# Sensor_Board.net
KiCad netlist of a schematic drawn in Altium Designer
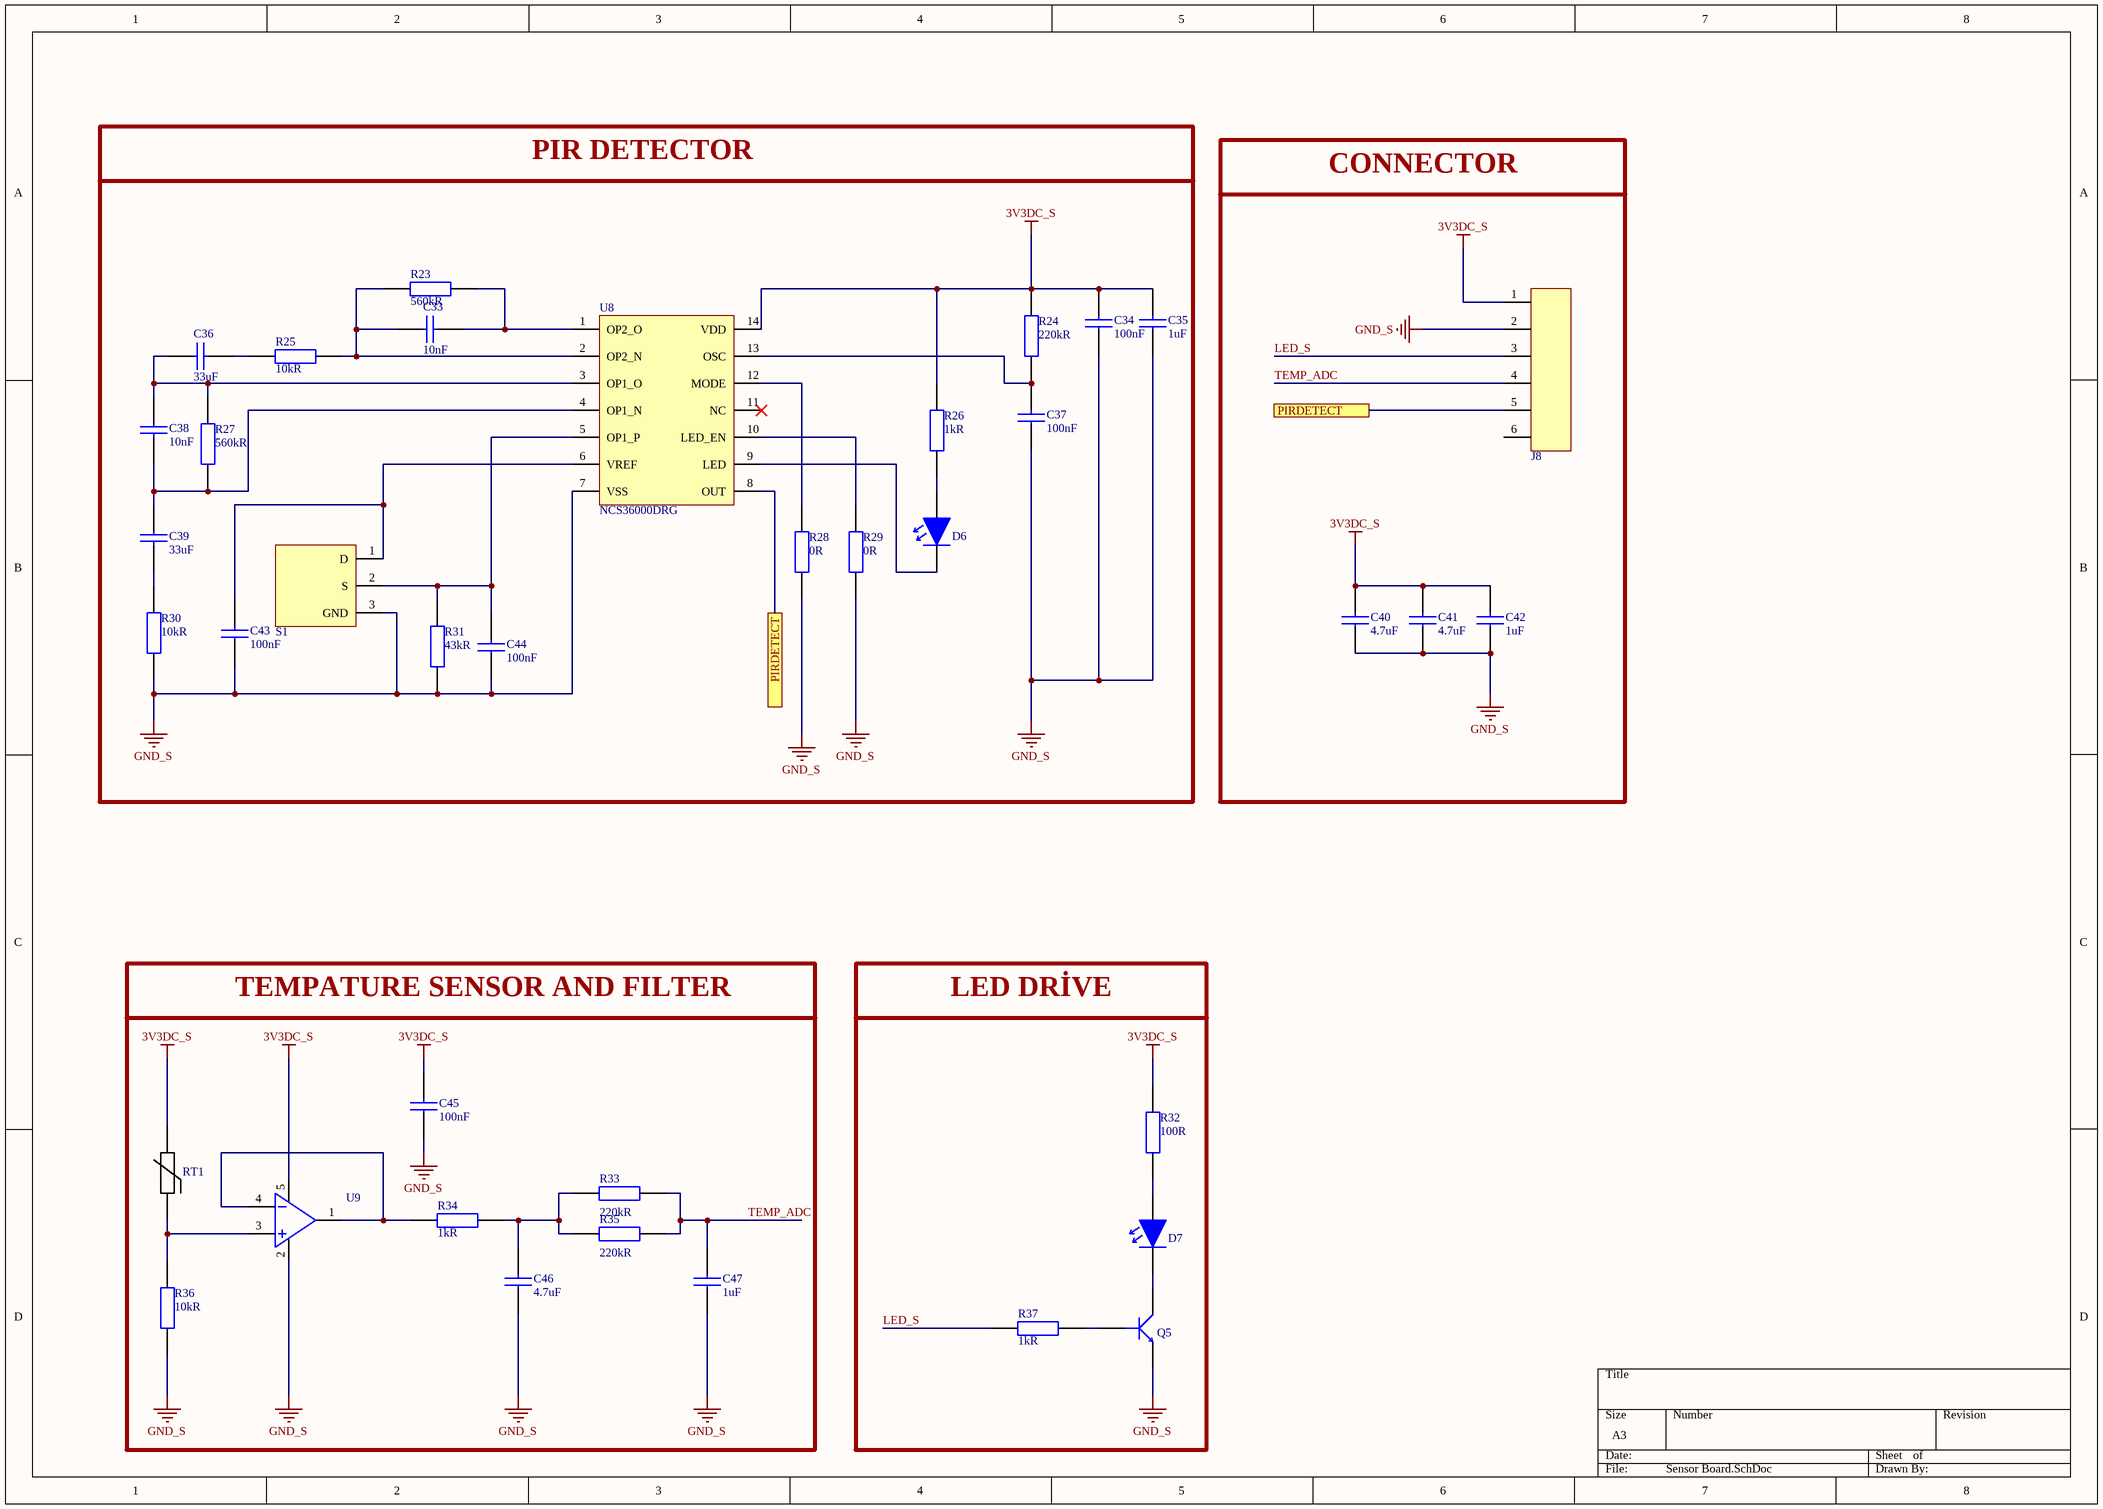
[diagram p0: Sensor Board.SchDoc]

(export (version "E")
  (design (tool "Eeschema 10.0.6"))
  (components
    (comp (ref "C33")
      (value "0603B103K160CT")
      (footprint "CAP_0603")
      (description "CAP CER 10nF %10 0603")
      (fields
        (field (name "MANUFACTURER") "Walsin Technologies")
        (field (name "TOLERANCE") "10%")
        (field (name "CAPACITANCE") "10nF")
        (field (name "DESIGNED BY") "TALAT")
      )
      (libsource (lib "Udemy_Library") (part "CAP CER 10nF 0603"))
    )
    (comp (ref "C34")
      (value "C0603C104K5RACTU")
      (footprint "CAP_0603")
      (description "CAP CER 100nF %10 0603 SMD")
      (fields
        (field (name "MANUFACTURER") "KEMET")
        (field (name "CAPACITANCE") "100nF")
        (field (name "TOLERANCE") "10%")
        (field (name "DESIGNED BY") "TALAT")
      )
      (libsource (lib "Udemy_Library") (part "CAP CER 100nF 0603"))
    )
    (comp (ref "C35")
      (value "CL21B105KBFNNNE")
      (footprint "CAP_0805")
      (description "CAP CER 1uF %10 0805")
      (fields
        (field (name "MANUFACTURER") "Samsung")
        (field (name "TOLERANCE") "10%")
        (field (name "CAPACITANCE") "1uF")
        (field (name "DESIGNED BY") "TALAT")
      )
      (libsource (lib "Udemy_Library") (part "CAP CER 1uF 0805"))
    )
    (comp (ref "C36")
      (value "C3216X5R1E336M160AC")
      (footprint "CAP_1206")
      (description "CAP CER 33uF %20 1206 SMD")
      (fields
        (field (name "MANUFACTURER") "TDK")
        (field (name "TOLERANCE") "20%")
        (field (name "CAPACITANCE") "33uF")
        (field (name "DESIGNED BY") "TALAT")
      )
      (libsource (lib "Udemy_Library") (part "CAP CER 33uF 1206"))
    )
    (comp (ref "C37")
      (value "C0603C104K5RACTU")
      (footprint "CAP_0603")
      (description "CAP CER 100nF %10 0603 SMD")
      (fields
        (field (name "MANUFACTURER") "KEMET")
        (field (name "CAPACITANCE") "100nF")
        (field (name "TOLERANCE") "10%")
        (field (name "DESIGNED BY") "TALAT")
      )
      (libsource (lib "Udemy_Library") (part "CAP CER 100nF 0603"))
    )
    (comp (ref "C38")
      (value "0603B103K160CT")
      (footprint "CAP_0603")
      (description "CAP CER 10nF %10 0603")
      (fields
        (field (name "MANUFACTURER") "Walsin Technologies")
        (field (name "TOLERANCE") "10%")
        (field (name "CAPACITANCE") "10nF")
        (field (name "DESIGNED BY") "TALAT")
      )
      (libsource (lib "Udemy_Library") (part "CAP CER 10nF 0603"))
    )
    (comp (ref "C39")
      (value "C3216X5R1E336M160AC")
      (footprint "CAP_1206")
      (description "CAP CER 33uF %20 1206 SMD")
      (fields
        (field (name "MANUFACTURER") "TDK")
        (field (name "TOLERANCE") "20%")
        (field (name "CAPACITANCE") "33uF")
        (field (name "DESIGNED BY") "TALAT")
      )
      (libsource (lib "Udemy_Library") (part "CAP CER 33uF 1206"))
    )
    (comp (ref "C40")
      (value "CL21A475KAQNNNE")
      (footprint "CAP_0805")
      (description "CAP CER 4.7uF %10 0805")
      (fields
        (field (name "MANUFACTURER") "Samsung")
        (field (name "TOLERANCE") "10%")
        (field (name "CAPACITANCE") "4.7uF")
        (field (name "DESIGNED BY") "TALAT")
      )
      (libsource (lib "Udemy_Library") (part "CAP CER 4.7uF 0805"))
    )
    (comp (ref "C41")
      (value "CL21A475KAQNNNE")
      (footprint "CAP_0805")
      (description "CAP CER 4.7uF %10 0805")
      (fields
        (field (name "MANUFACTURER") "Samsung")
        (field (name "TOLERANCE") "10%")
        (field (name "CAPACITANCE") "4.7uF")
        (field (name "DESIGNED BY") "TALAT")
      )
      (libsource (lib "Udemy_Library") (part "CAP CER 4.7uF 0805"))
    )
    (comp (ref "C42")
      (value "CL21B105KBFNNNE")
      (footprint "CAP_0805")
      (description "CAP CER 1uF %10 0805")
      (fields
        (field (name "MANUFACTURER") "Samsung")
        (field (name "TOLERANCE") "10%")
        (field (name "CAPACITANCE") "1uF")
        (field (name "DESIGNED BY") "TALAT")
      )
      (libsource (lib "Udemy_Library") (part "CAP CER 1uF 0805"))
    )
    (comp (ref "C43")
      (value "C0603C104K5RACTU")
      (footprint "CAP_0603")
      (description "CAP CER 100nF %10 0603 SMD")
      (fields
        (field (name "MANUFACTURER") "KEMET")
        (field (name "CAPACITANCE") "100nF")
        (field (name "TOLERANCE") "10%")
        (field (name "DESIGNED BY") "TALAT")
      )
      (libsource (lib "Udemy_Library") (part "CAP CER 100nF 0603"))
    )
    (comp (ref "C44")
      (value "C0603C104K5RACTU")
      (footprint "CAP_0603")
      (description "CAP CER 100nF %10 0603 SMD")
      (fields
        (field (name "MANUFACTURER") "KEMET")
        (field (name "CAPACITANCE") "100nF")
        (field (name "TOLERANCE") "10%")
        (field (name "DESIGNED BY") "TALAT")
      )
      (libsource (lib "Udemy_Library") (part "CAP CER 100nF 0603"))
    )
    (comp (ref "C45")
      (value "CL21B104KBCNNNC")
      (footprint "CAP_0805")
      (description "CAP CER 100nF %10 0805")
      (fields
        (field (name "MANUFACTURER") "Samsung")
        (field (name "TOLERANCE") "10%")
        (field (name "CAPACITANCE") "100nF")
        (field (name "DESIGNED BY") "TALAT")
      )
      (libsource (lib "Udemy_Library") (part "CAP CER 100nF 0805"))
    )
    (comp (ref "C46")
      (value "CL21A475KAQNNNE")
      (footprint "CAP_0805")
      (description "CAP CER 4.7uF %10 0805")
      (fields
        (field (name "MANUFACTURER") "Samsung")
        (field (name "TOLERANCE") "10%")
        (field (name "CAPACITANCE") "4.7uF")
        (field (name "DESIGNED BY") "TALAT")
      )
      (libsource (lib "Udemy_Library") (part "CAP CER 4.7uF 0805"))
    )
    (comp (ref "C47")
      (value "CL21B105KBFNNNE")
      (footprint "CAP_0805")
      (description "CAP CER 1uF %10 0805")
      (fields
        (field (name "MANUFACTURER") "Samsung")
        (field (name "TOLERANCE") "10%")
        (field (name "CAPACITANCE") "1uF")
        (field (name "DESIGNED BY") "TALAT")
      )
      (libsource (lib "Udemy_Library") (part "CAP CER 1uF 0805"))
    )
    (comp (ref "D6")
      (value "LTST-C171GKT")
      (footprint "LED_GREEN_0805")
      (description "Green 0805 130 º Min 5 mcd Typical 12 mcd Water Clear Lens SMT LED")
      (fields (field (name "MANUFACTURER") "Vishay Lite-On") (field (name "DESIGNED BY") "TALAT"))
      (libsource (lib "Udemy_Library") (part "LED GREEN 0805"))
    )
    (comp (ref "D7")
      (value "LH R974-LP-1")
      (footprint "LED_RED_0805")
      (description "LED Uni-Color Hyper Red 660nm 2-Pin Chip 0805(2012Metric) T/R")
      (fields (field (name "MANUFACTURER") "Osram Opto") (field (name "DESIGNED BY") "TALAT"))
      (libsource (lib "Udemy_Library") (part "LED RED 0805"))
    )
    (comp (ref "J8")
      (value "64800611622")
      (footprint "64800611622")
      (description "1.50mm 6PIN Connector")
      (fields (field (name "MANUFACTURER") "Wurth Electronics") (field (name "DESIGNED BY") "TALAT"))
      (libsource (lib "Udemy_Library") (part "64800611622_conn_6pin"))
    )
    (comp (ref "Q5")
      (value "MMBT3904-7-F")
      (footprint "SOT-23F")
      (description "Transistor General Purpose BJT NPN 40 Volt 0.2A Automotive 3-Pin SOT-23")
      (fields (field (name "MANUFACTURER") "Diodes Zetex") (field (name "DESIGNED BY") "TALAT"))
      (libsource (lib "Udemy_Library") (part "MMBT3904-7-F"))
    )
    (comp (ref "R23")
      (value "RC0603JR-07560KL")
      (footprint "RES_0603")
      (description "RES SMD 560K OHM 5% 1/10W 0603")
      (fields
        (field (name "MANUFACTURER") "Yageo")
        (field (name "TOLERANCE") "5%")
        (field (name "RESISTANCE") "560kR")
        (field (name "DESIGNED BY") "TALAT")
      )
      (libsource (lib "") (part "RES 560K OHM 0603_1"))
    )
    (comp (ref "R24")
      (value "RC0603JR-07220KL")
      (footprint "RES_0603")
      (description "RES 220K %5 OHM 0603 SMD")
      (fields
        (field (name "MANUFACTURER") "Yageo")
        (field (name "TOLERANCE") "5%")
        (field (name "RESISTANCE") "220kR")
      )
      (libsource (lib "") (part "RES 220K OHM 0603_1"))
    )
    (comp (ref "R25")
      (value "RC0603FR-0710KL")
      (footprint "RES_0603")
      (description "RES 10K %1 OHM 0603 SMD")
      (fields
        (field (name "MANUFACTURER") "Yageo")
        (field (name "TOLERANCE") "1%")
        (field (name "RESISTANCE") "10kR")
        (field (name "DESIGNED BY") "TALAT")
      )
      (libsource (lib "") (part "RES 10K OHM 0603_2"))
    )
    (comp (ref "R26")
      (value "RC0603FR-0710KL")
      (footprint "RES_0603")
      (description "RES 1K %1 OHM 0603 SMD")
      (fields
        (field (name "MANUFACTURER") "Yageo")
        (field (name "MANUFACTURER PART NUMBER") "RC0603JR-071KL")
        (field (name "RESISTANCE") "1kR")
        (field (name "DESIGNED BY") "TALAT")
      )
      (libsource (lib "") (part "RES 1K OHM 0603_1"))
    )
    (comp (ref "R27")
      (value "RC0603JR-07560KL")
      (footprint "RES_0603")
      (description "RES SMD 560K OHM 5% 1/10W 0603")
      (fields
        (field (name "MANUFACTURER") "Yageo")
        (field (name "TOLERANCE") "5%")
        (field (name "RESISTANCE") "560kR")
        (field (name "DESIGNED BY") "TALAT")
      )
      (libsource (lib "Udemy_Library") (part "RES 560K OHM 0603"))
    )
    (comp (ref "R28")
      (value "RC0603JR-070RL")
      (footprint "RES_0603")
      (description "RES 0 %1 OHM 0603 SMD")
      (fields
        (field (name "MANUFACTURER") "Yageo")
        (field (name "TOLERANCE") "1%")
        (field (name "RESISTANCE") "0R")
        (field (name "DESIGNED BY") "TALAT")
      )
      (libsource (lib "Udemy_Library") (part "RES 0 OHM 0603"))
    )
    (comp (ref "R29")
      (value "RC0603JR-070RL")
      (footprint "RES_0603")
      (description "RES 0 %1 OHM 0603 SMD")
      (fields
        (field (name "MANUFACTURER") "Yageo")
        (field (name "TOLERANCE") "1%")
        (field (name "RESISTANCE") "0R")
        (field (name "DESIGNED BY") "TALAT")
      )
      (libsource (lib "Udemy_Library") (part "RES 0 OHM 0603"))
    )
    (comp (ref "R30")
      (value "RC0603FR-0710KL")
      (footprint "RES_0603")
      (description "RES 10K %1 OHM 0603 SMD")
      (fields
        (field (name "MANUFACTURER") "Yageo")
        (field (name "TOLERANCE") "1%")
        (field (name "RESISTANCE") "10kR")
        (field (name "DESIGNED BY") "TALAT")
      )
      (libsource (lib "") (part "RES 10K OHM 0603_1"))
    )
    (comp (ref "R31")
      (value "RC0603JR-0743KL")
      (footprint "RES_0603")
      (description "RES 43K %5 OHM 0603 SMD")
      (fields
        (field (name "MANUFACTURER") "Yageo")
        (field (name "TOLERANCE") "5%")
        (field (name "RESISTANCE") "43kR")
        (field (name "DESIGNED BY") "TALAT")
      )
      (libsource (lib "Udemy_Library") (part "RES 43K OHM 0603"))
    )
    (comp (ref "R32")
      (value "RC0603JR-07100RL")
      (footprint "RES_0603")
      (description "RES 100 %5 OHM 0603 SMD")
      (fields
        (field (name "MANUFACTURER") "Yageo")
        (field (name "TOLERANCE") "5%")
        (field (name "RESISTANCE") "100R")
        (field (name "DESIGNED BY") "TALAT")
      )
      (libsource (lib "Udemy_Library") (part "RES 100 OHM 0603"))
    )
    (comp (ref "R33")
      (value "RC0603JR-07220KL")
      (footprint "RES_0603")
      (description "RES 220K %5 OHM 0603 SMD")
      (fields
        (field (name "MANUFACTURER") "Yageo")
        (field (name "TOLERANCE") "5%")
        (field (name "RESISTANCE") "220kR")
      )
      (libsource (lib "Udemy_Library") (part "RES 220K OHM 0603"))
    )
    (comp (ref "R34")
      (value "RC0603FR-0710KL")
      (footprint "RES_0603")
      (description "RES 1K %1 OHM 0603 SMD")
      (fields
        (field (name "MANUFACTURER") "Yageo")
        (field (name "MANUFACTURER PART NUMBER") "RC0603JR-071KL")
        (field (name "RESISTANCE") "1kR")
        (field (name "DESIGNED BY") "TALAT")
      )
      (libsource (lib "Udemy_Library") (part "RES 1K OHM 0603"))
    )
    (comp (ref "R35")
      (value "RC0603JR-07220KL")
      (footprint "RES_0603")
      (description "RES 220K %5 OHM 0603 SMD")
      (fields
        (field (name "MANUFACTURER") "Yageo")
        (field (name "TOLERANCE") "5%")
        (field (name "RESISTANCE") "220kR")
      )
      (libsource (lib "Udemy_Library") (part "RES 220K OHM 0603"))
    )
    (comp (ref "R36")
      (value "RC0603FR-0710KL")
      (footprint "RES_0603")
      (description "RES 10K %1 OHM 0603 SMD")
      (fields
        (field (name "MANUFACTURER") "Yageo")
        (field (name "TOLERANCE") "1%")
        (field (name "RESISTANCE") "10kR")
        (field (name "DESIGNED BY") "TALAT")
      )
      (libsource (lib "Udemy_Library") (part "RES 10K OHM 0603"))
    )
    (comp (ref "R37")
      (value "RC0603FR-0710KL")
      (footprint "RES_0603")
      (description "RES 1K %1 OHM 0603 SMD")
      (fields
        (field (name "MANUFACTURER") "Yageo")
        (field (name "MANUFACTURER PART NUMBER") "RC0603JR-071KL")
        (field (name "RESISTANCE") "1kR")
        (field (name "DESIGNED BY") "TALAT")
      )
      (libsource (lib "Udemy_Library") (part "RES 1K OHM 0603"))
    )
    (comp (ref "RT1")
      (value "TFPT1206L1002FM")
      (footprint "RES_1206")
      (description "Thermistor PTC 10K Ohm 1% 1206")
      (fields
        (field (name "MANUFACTURER") "Vishay Dale")
        (field (name "TOLERANCE") "1%")
        (field (name "DESIGNED BY") "TALAT")
      )
      (libsource (lib "Udemy_Library") (part "TFPT1206L1002FM"))
    )
    (comp (ref "S1")
      (value "LHI 878/3902")
      (footprint "LHI 878")
      (description "SENSOR PYRO DETECTOR DUAL MOTION")
      (libsource (lib "Udemy_Library") (part "LHI 878/3902"))
    )
    (comp (ref "U8")
      (value "NCS36000DRG")
      (footprint "SOIC14")
      (description "PIR Controller Low Noise Amplifiers and LDO Regulator 14-Pin SOIC N T/R")
      (fields (field (name "MANUFACTURER") "ON Semiconductor") (field (name "DESIGNED BY") "TALAT"))
      (libsource (lib "Udemy_Library") (part "NCS36000"))
    )
    (comp (ref "U9")
      (value "OPA314AIDBVR")
      (footprint "SOT23-5")
      (description "Op Amp OPA314")
      (fields (field (name "MANUFACTURER") "Texas Instruments") (field (name "DESIGNED BY") "TALAT"))
      (libsource (lib "Udemy_Library") (part "OPA314"))
    )
  )
  (nets
    (net (code "1") (name "/LED_S") (class "Default")
      (node (ref "J8") (pin "3") (pintype "power_in"))
      (node (ref "R37") (pin "1") (pinfunction "1_1") (pintype "passive"))
    )
    (net (code "2") (name "/PIRDETECT") (class "Default")
      (node (ref "J8") (pin "5") (pintype "power_in"))
      (node (ref "U8") (pin "8") (pinfunction "OUT_8") (pintype "passive"))
    )
    (net (code "3") (name "/TEMP_ADC") (class "Default")
      (node (ref "C47") (pin "2") (pinfunction "2_2") (pintype "passive"))
      (node (ref "J8") (pin "4") (pintype "power_in"))
      (node (ref "R33") (pin "2") (pinfunction "2_2") (pintype "passive"))
      (node (ref "R35") (pin "2") (pinfunction "2_2") (pintype "passive"))
    )
    (net (code "4") (name "3V3DC_S") (class "Default")
      (node (ref "C34") (pin "2") (pinfunction "2_2") (pintype "passive"))
      (node (ref "C35") (pin "2") (pinfunction "2_2") (pintype "passive"))
      (node (ref "C40") (pin "2") (pinfunction "2_2") (pintype "passive"))
      (node (ref "C41") (pin "2") (pinfunction "2_2") (pintype "passive"))
      (node (ref "C42") (pin "2") (pinfunction "2_2") (pintype "passive"))
      (node (ref "C45") (pin "2") (pinfunction "2_2") (pintype "passive"))
      (node (ref "J8") (pin "1") (pintype "power_in"))
      (node (ref "R24") (pin "2") (pinfunction "2_2") (pintype "passive"))
      (node (ref "R26") (pin "2") (pinfunction "2_2") (pintype "passive"))
      (node (ref "R32") (pin "2") (pinfunction "2_2") (pintype "passive"))
      (node (ref "RT1") (pin "2") (pinfunction "2_2") (pintype "passive"))
      (node (ref "U8") (pin "14") (pinfunction "VDD_14") (pintype "passive"))
      (node (ref "U9") (pin "5") (pinfunction "5_5") (pintype "passive"))
    )
    (net (code "5") (name "GND_S") (class "Default")
      (node (ref "C34") (pin "1") (pinfunction "1_1") (pintype "passive"))
      (node (ref "C35") (pin "1") (pinfunction "1_1") (pintype "passive"))
      (node (ref "C37") (pin "1") (pinfunction "1_1") (pintype "passive"))
      (node (ref "C40") (pin "1") (pinfunction "1_1") (pintype "passive"))
      (node (ref "C41") (pin "1") (pinfunction "1_1") (pintype "passive"))
      (node (ref "C42") (pin "1") (pinfunction "1_1") (pintype "passive"))
      (node (ref "C43") (pin "1") (pinfunction "1_1") (pintype "passive"))
      (node (ref "C44") (pin "1") (pinfunction "1_1") (pintype "passive"))
      (node (ref "C45") (pin "1") (pinfunction "1_1") (pintype "passive"))
      (node (ref "C46") (pin "1") (pinfunction "1_1") (pintype "passive"))
      (node (ref "C47") (pin "1") (pinfunction "1_1") (pintype "passive"))
      (node (ref "J8") (pin "2") (pintype "power_in"))
      (node (ref "Q5") (pin "2") (pinfunction "E_2") (pintype "power_in"))
      (node (ref "R28") (pin "1") (pinfunction "1_1") (pintype "passive"))
      (node (ref "R29") (pin "1") (pinfunction "1_1") (pintype "passive"))
      (node (ref "R30") (pin "2") (pinfunction "2_2") (pintype "passive"))
      (node (ref "R31") (pin "1") (pinfunction "1_1") (pintype "passive"))
      (node (ref "R36") (pin "1") (pinfunction "1_1") (pintype "passive"))
      (node (ref "S1") (pin "3") (pinfunction "GND_3") (pintype "passive"))
      (node (ref "U8") (pin "7") (pinfunction "VSS_7") (pintype "passive"))
      (node (ref "U9") (pin "2") (pinfunction "2_2") (pintype "passive"))
    )
    (net (code "6") (name "Net-(C36-Pad2)") (class "Default")
      (node (ref "C36") (pin "2") (pinfunction "2_2") (pintype "passive"))
      (node (ref "R25") (pin "1") (pinfunction "1_1") (pintype "passive"))
    )
    (net (code "7") (name "Net-(C39-Pad2)") (class "Default")
      (node (ref "C39") (pin "2") (pinfunction "2_2") (pintype "passive"))
      (node (ref "R30") (pin "1") (pinfunction "1_1") (pintype "passive"))
    )
    (net (code "8") (name "Net-(C46-Pad2)") (class "Default")
      (node (ref "C46") (pin "2") (pinfunction "2_2") (pintype "passive"))
      (node (ref "R33") (pin "1") (pinfunction "1_1") (pintype "passive"))
      (node (ref "R34") (pin "2") (pinfunction "2_2") (pintype "passive"))
      (node (ref "R35") (pin "1") (pinfunction "1_1") (pintype "passive"))
    )
    (net (code "9") (name "Net-(D6-Pad2)") (class "Default")
      (node (ref "D6") (pin "2") (pinfunction "2_2") (pintype "power_in"))
      (node (ref "R26") (pin "1") (pinfunction "1_1") (pintype "passive"))
    )
    (net (code "10") (name "Net-(D7-Pad2)") (class "Default")
      (node (ref "D7") (pin "2") (pinfunction "2_2") (pintype "power_in"))
      (node (ref "R32") (pin "1") (pinfunction "1_1") (pintype "passive"))
    )
    (net (code "11") (name "Net-(Q5-B)") (class "Default")
      (node (ref "Q5") (pin "1") (pinfunction "B_1") (pintype "power_in"))
      (node (ref "R37") (pin "2") (pinfunction "2_2") (pintype "passive"))
    )
    (net (code "12") (name "Net-(Q5-C)") (class "Default")
      (node (ref "D7") (pin "1") (pinfunction "1_1") (pintype "power_in"))
      (node (ref "Q5") (pin "3") (pinfunction "C_3") (pintype "power_in"))
    )
    (net (code "13") (name "Net-(R34-Pad1)") (class "Default")
      (node (ref "R34") (pin "1") (pinfunction "1_1") (pintype "passive"))
      (node (ref "U9") (pin "1") (pinfunction "1_1") (pintype "passive"))
      (node (ref "U9") (pin "4") (pinfunction "4_4") (pintype "passive"))
    )
    (net (code "14") (name "Net-(R36-Pad2)") (class "Default")
      (node (ref "R36") (pin "2") (pinfunction "2_2") (pintype "passive"))
      (node (ref "RT1") (pin "1") (pinfunction "1_1") (pintype "passive"))
      (node (ref "U9") (pin "3") (pinfunction "3_3") (pintype "passive"))
    )
    (net (code "15") (name "Net-(S1-D)") (class "Default")
      (node (ref "C43") (pin "2") (pinfunction "2_2") (pintype "passive"))
      (node (ref "S1") (pin "1") (pinfunction "D_1") (pintype "passive"))
      (node (ref "U8") (pin "6") (pinfunction "VREF_6") (pintype "passive"))
    )
    (net (code "16") (name "Net-(S1-S)") (class "Default")
      (node (ref "C44") (pin "2") (pinfunction "2_2") (pintype "passive"))
      (node (ref "R31") (pin "2") (pinfunction "2_2") (pintype "passive"))
      (node (ref "S1") (pin "2") (pinfunction "S_2") (pintype "passive"))
      (node (ref "U8") (pin "5") (pinfunction "OP1_P_5") (pintype "passive"))
    )
    (net (code "17") (name "Net-(U8-LED)") (class "Default")
      (node (ref "D6") (pin "1") (pinfunction "1_1") (pintype "power_in"))
      (node (ref "U8") (pin "9") (pinfunction "LED_9") (pintype "passive"))
    )
    (net (code "18") (name "Net-(U8-LED_EN)") (class "Default")
      (node (ref "R29") (pin "2") (pinfunction "2_2") (pintype "passive"))
      (node (ref "U8") (pin "10") (pinfunction "LED_EN_10") (pintype "passive"))
    )
    (net (code "19") (name "Net-(U8-MODE)") (class "Default")
      (node (ref "R28") (pin "2") (pinfunction "2_2") (pintype "passive"))
      (node (ref "U8") (pin "12") (pinfunction "MODE_12") (pintype "passive"))
    )
    (net (code "20") (name "Net-(U8-OP1_N)") (class "Default")
      (node (ref "C38") (pin "2") (pinfunction "2_2") (pintype "passive"))
      (node (ref "C39") (pin "1") (pinfunction "1_1") (pintype "passive"))
      (node (ref "R27") (pin "2") (pinfunction "2_2") (pintype "passive"))
      (node (ref "U8") (pin "4") (pinfunction "OP1_N_4") (pintype "passive"))
    )
    (net (code "21") (name "Net-(U8-OP1_O)") (class "Default")
      (node (ref "C36") (pin "1") (pinfunction "1_1") (pintype "passive"))
      (node (ref "C38") (pin "1") (pinfunction "1_1") (pintype "passive"))
      (node (ref "R27") (pin "1") (pinfunction "1_1") (pintype "passive"))
      (node (ref "U8") (pin "3") (pinfunction "OP1_O_3") (pintype "passive"))
    )
    (net (code "22") (name "Net-(U8-OP2_N)") (class "Default")
      (node (ref "C33") (pin "1") (pinfunction "1_1") (pintype "passive"))
      (node (ref "R23") (pin "1") (pinfunction "1_1") (pintype "passive"))
      (node (ref "R25") (pin "2") (pinfunction "2_2") (pintype "passive"))
      (node (ref "U8") (pin "2") (pinfunction "OP2_N_2") (pintype "passive"))
    )
    (net (code "23") (name "Net-(U8-OP2_O)") (class "Default")
      (node (ref "C33") (pin "2") (pinfunction "2_2") (pintype "passive"))
      (node (ref "R23") (pin "2") (pinfunction "2_2") (pintype "passive"))
      (node (ref "U8") (pin "1") (pinfunction "OP2_O_1") (pintype "passive"))
    )
    (net (code "24") (name "Net-(U8-OSC)") (class "Default")
      (node (ref "C37") (pin "2") (pinfunction "2_2") (pintype "passive"))
      (node (ref "R24") (pin "1") (pinfunction "1_1") (pintype "passive"))
      (node (ref "U8") (pin "13") (pinfunction "OSC_13") (pintype "passive"))
    )
    (net (code "25") (name "unconnected-(J8-Pad6)") (class "Default")
      (node (ref "J8") (pin "6") (pintype "power_in"))
    )
    (net (code "26") (name "unconnected-(U8-NC-Pad11)") (class "Default")
      (node (ref "U8") (pin "11") (pinfunction "NC_11") (pintype "passive+no_connect"))
    )
  )
)
